# mini-v1_11-macrofab.net
KiCad netlist of a schematic drawn in EAGLE
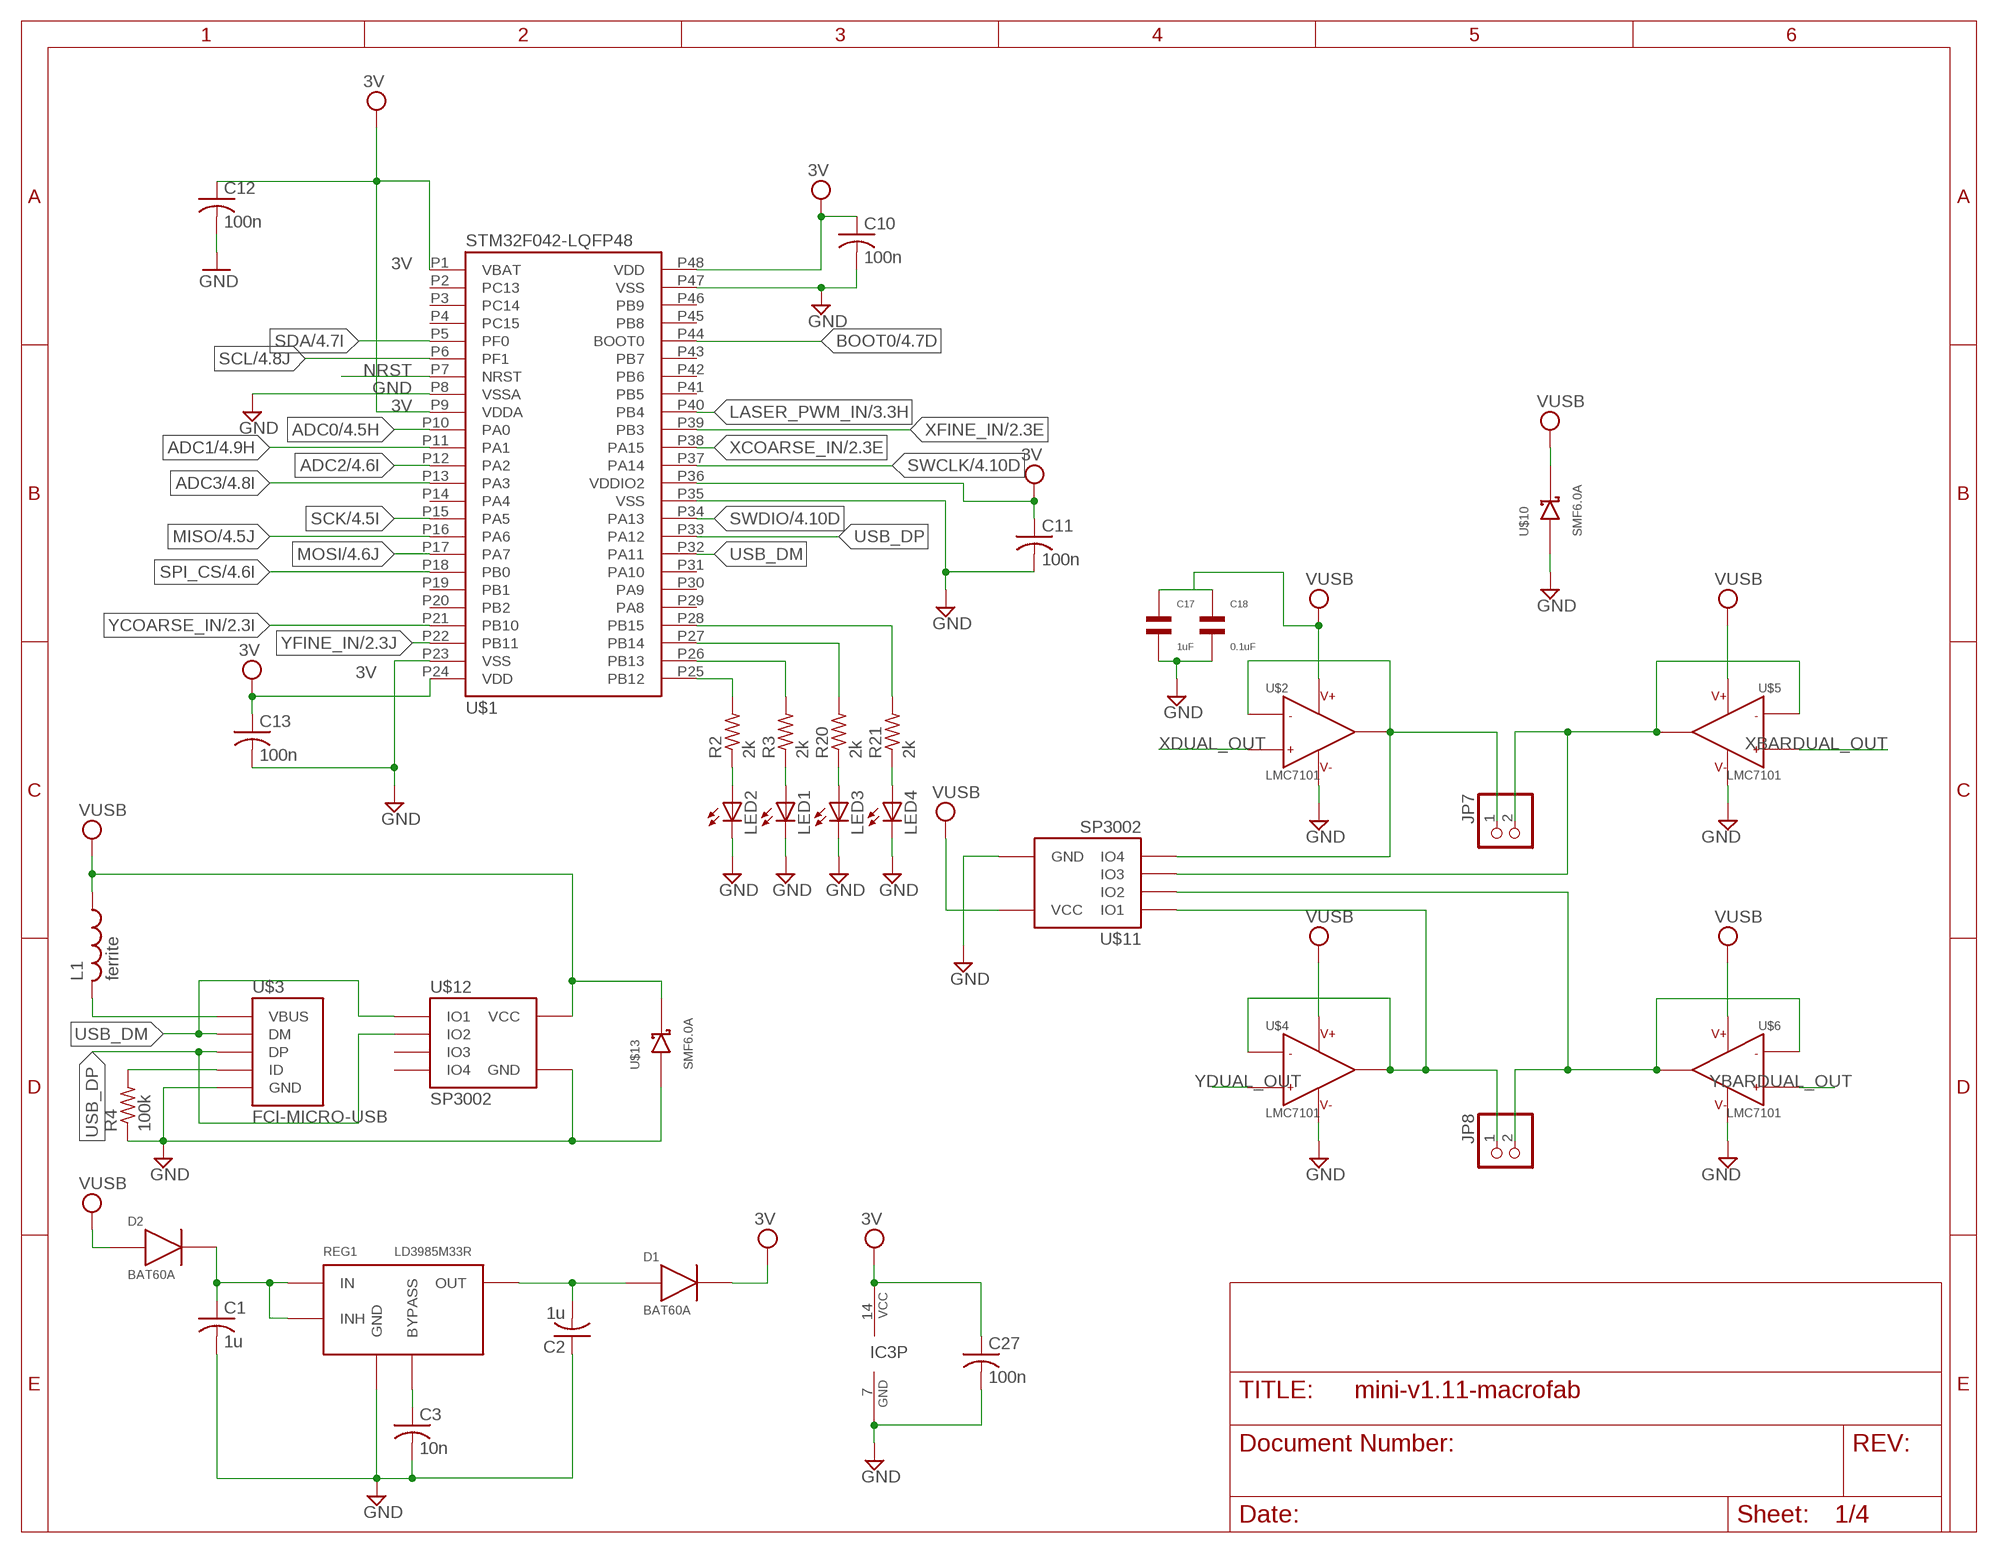
[diagram p0: schematic, sheet 1]
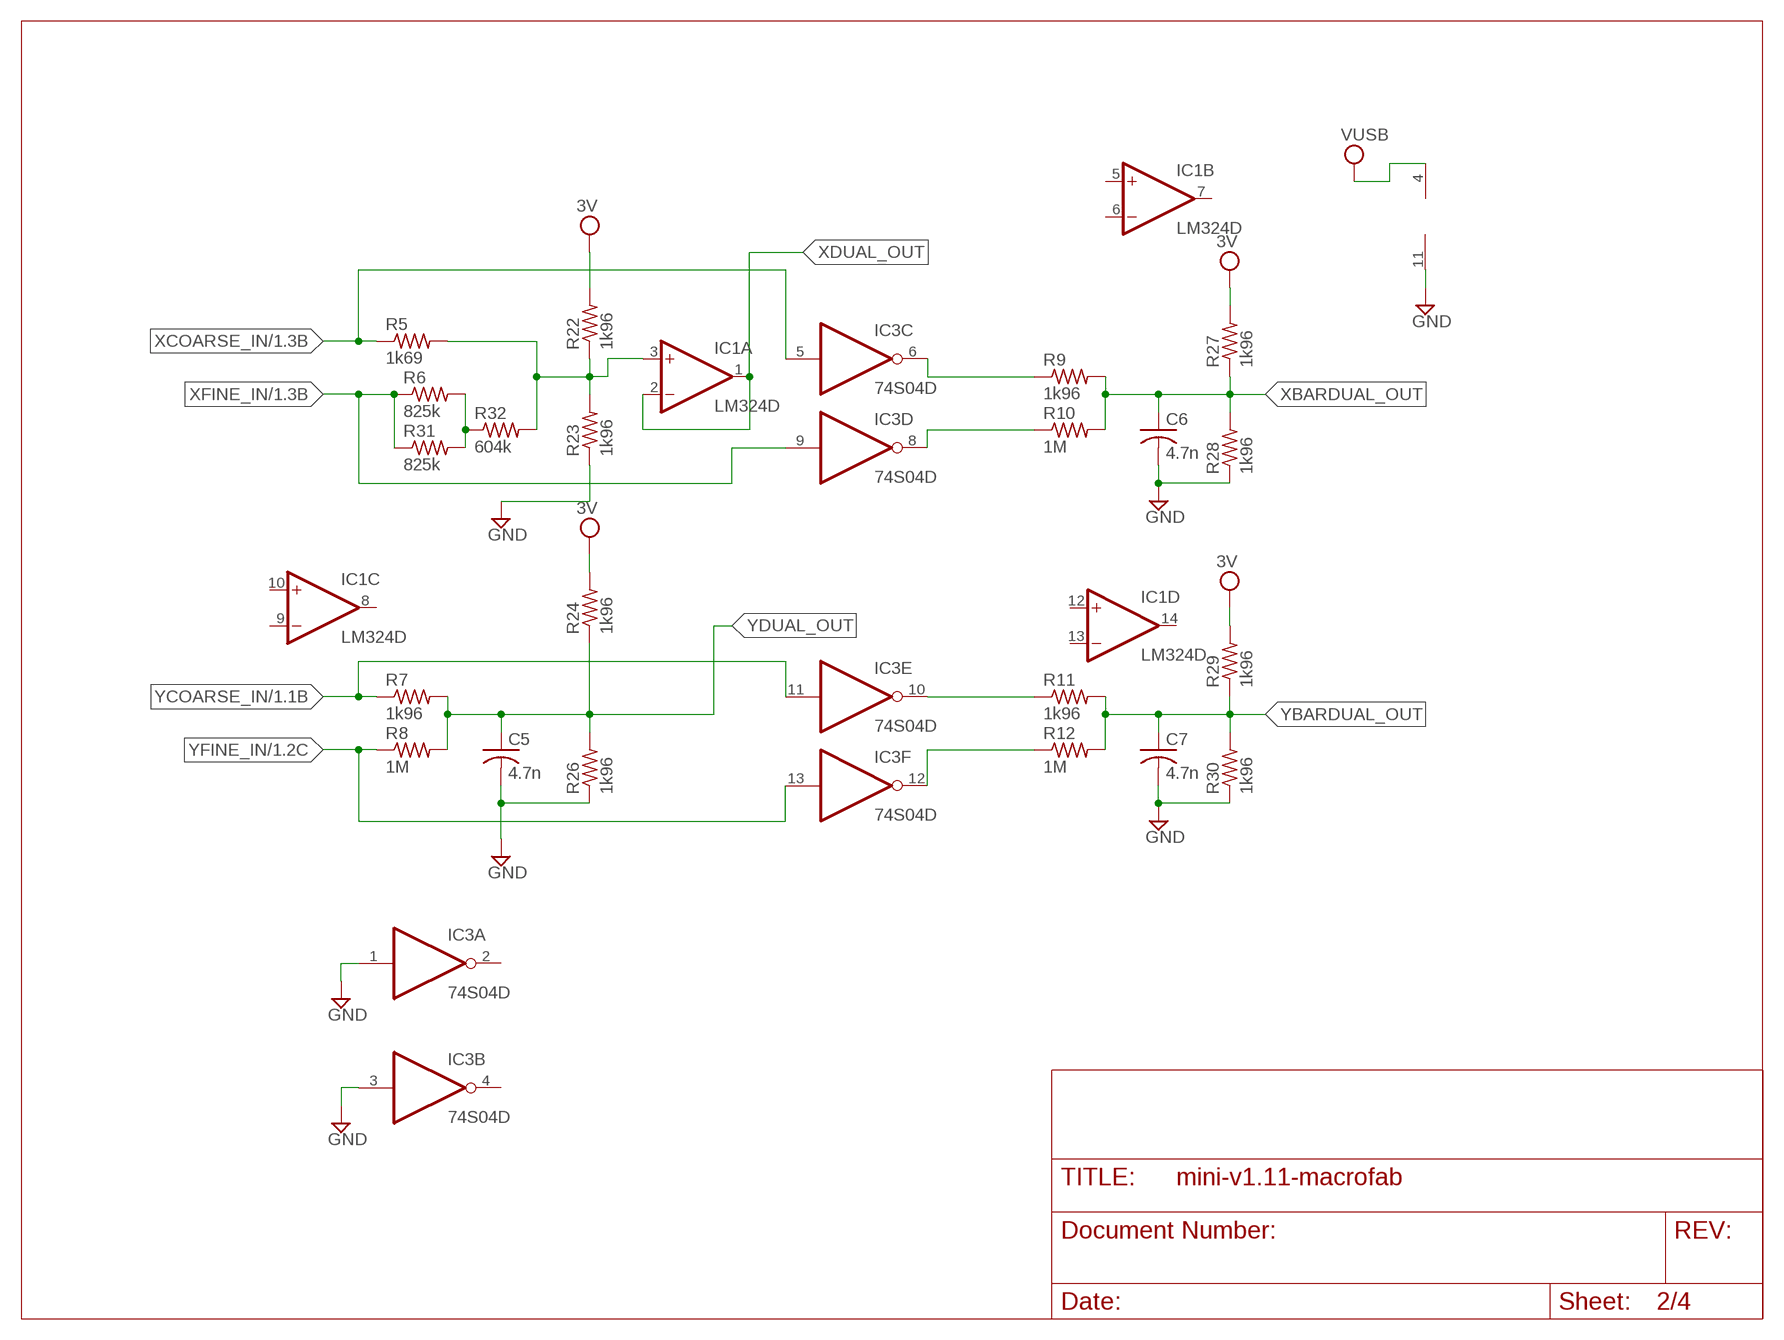
[diagram p1: schematic, sheet 2]
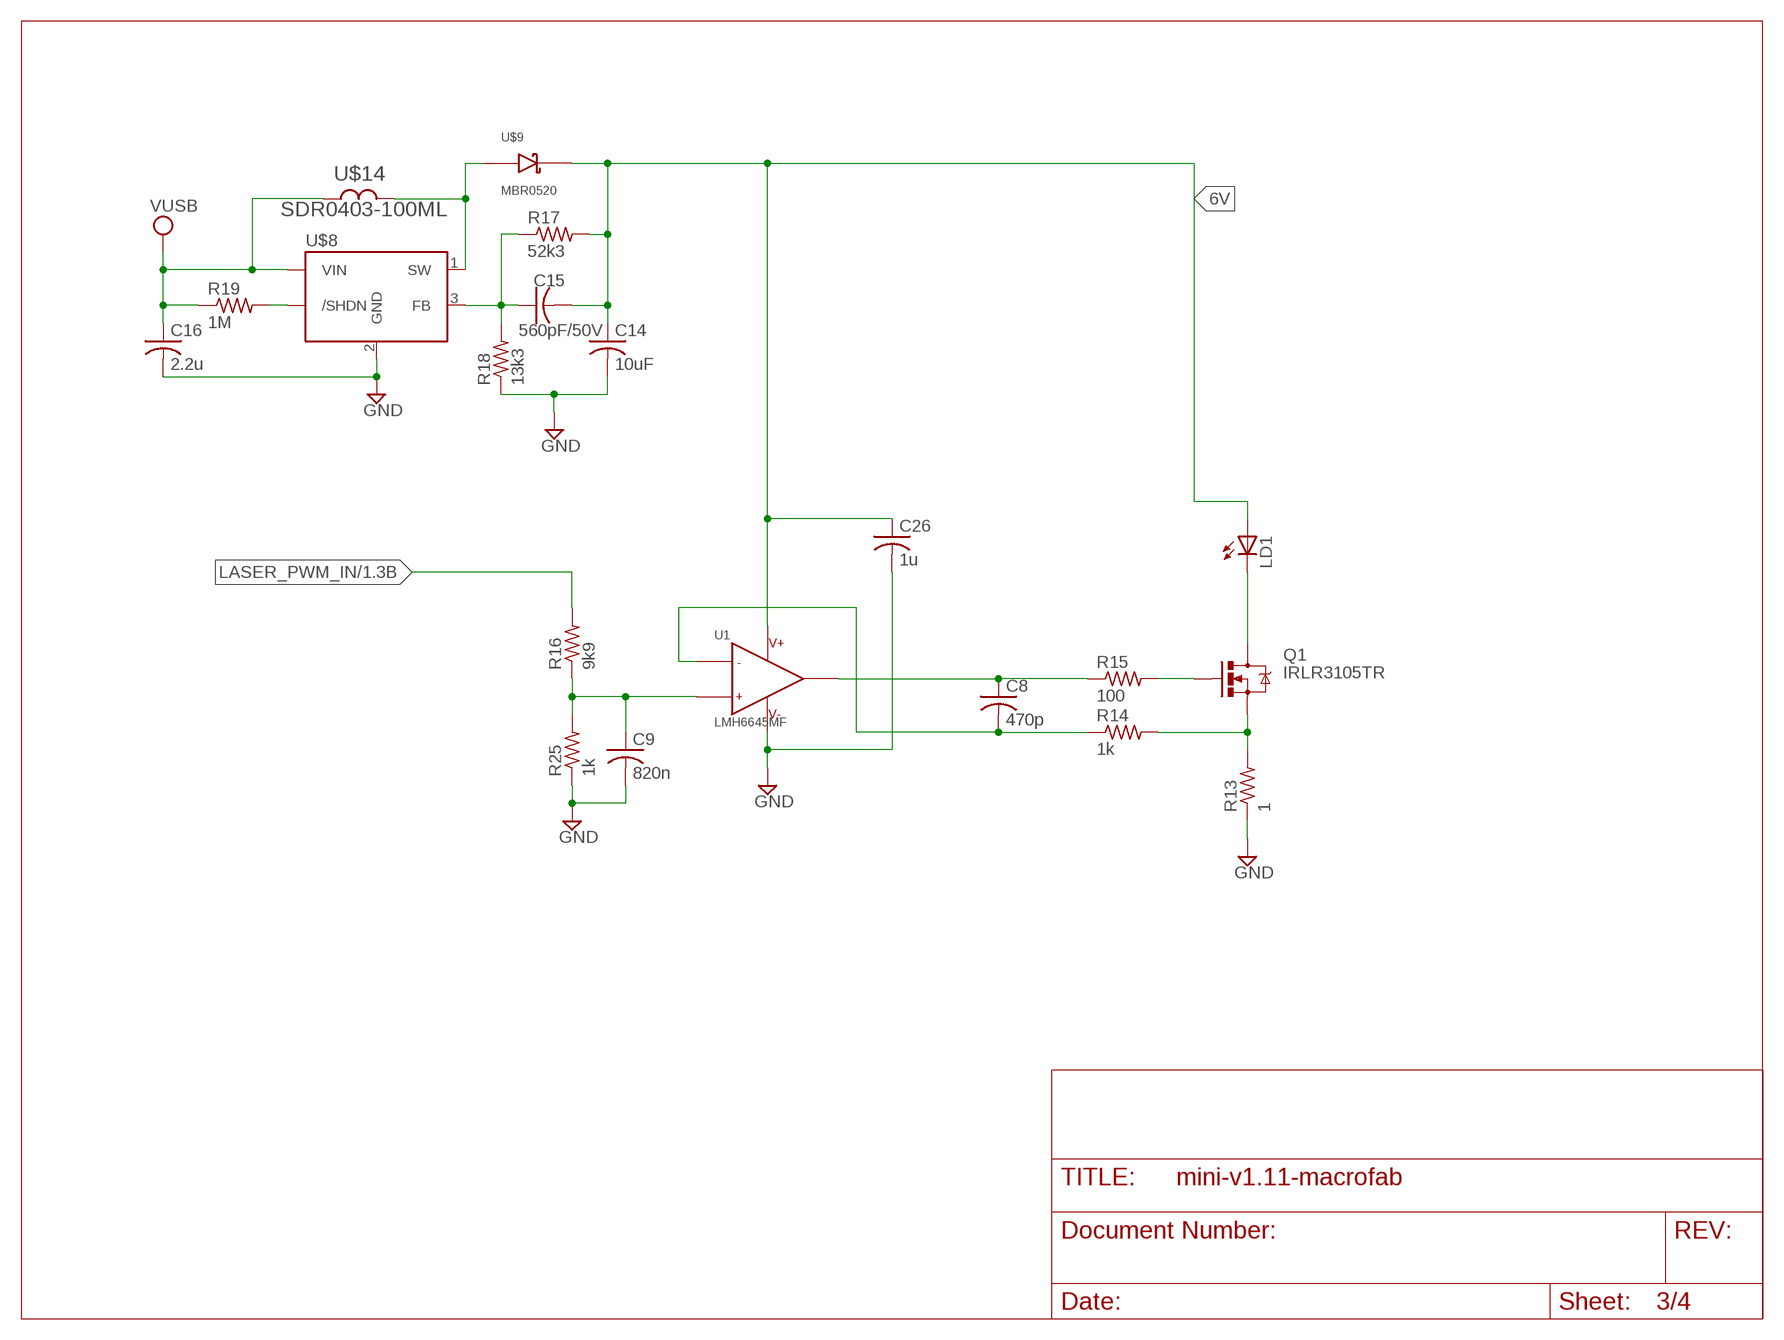
[diagram p2: schematic, sheet 3]
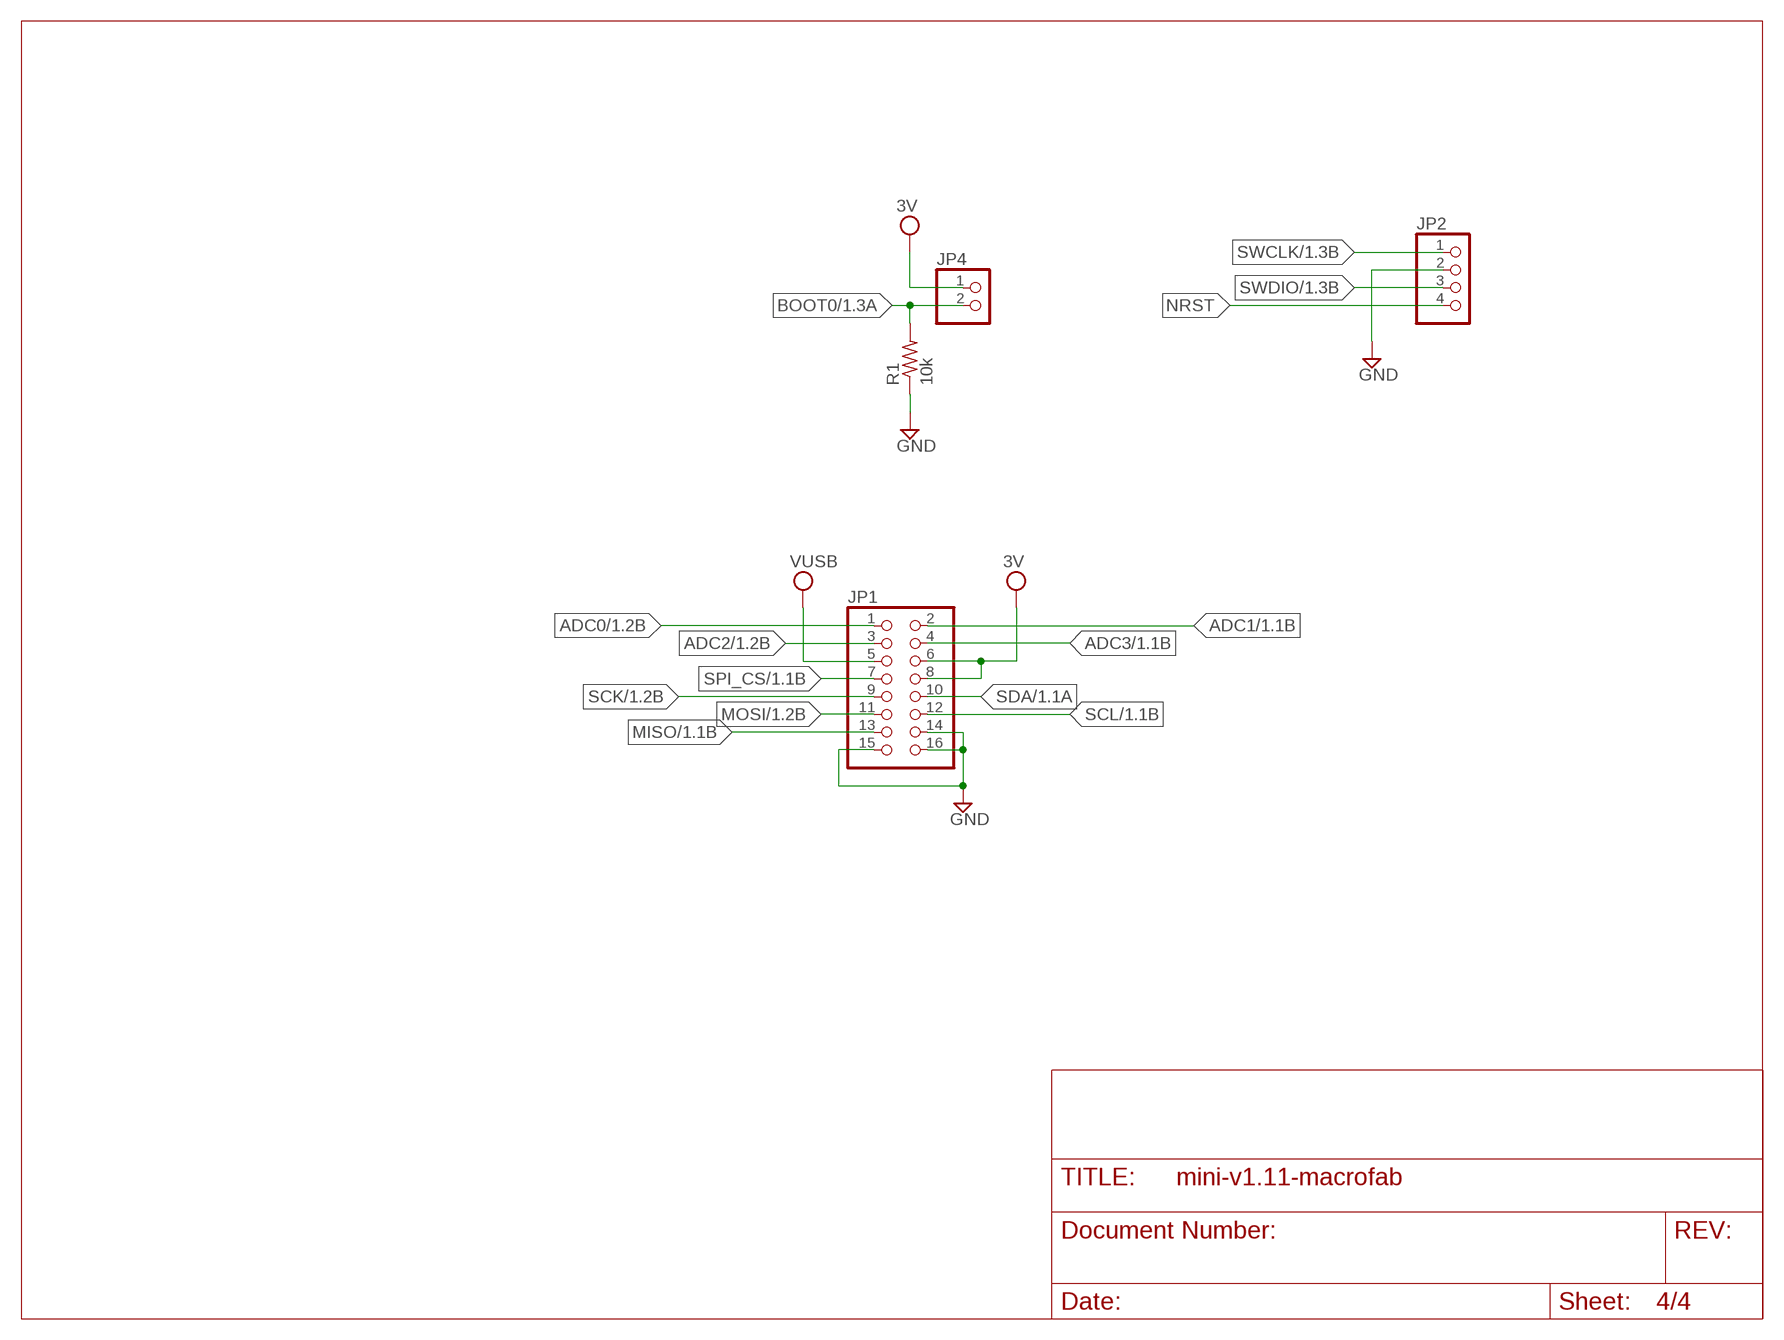
[diagram p3: schematic, sheet 4]

(export (version "E")
  (design (tool "Eeschema 10.0.6"))
  (components
    (comp (ref "C5")
      (value "4.7n")
      (footprint "eagle-import:C0603")
      (libsource (lib "eagle-import") (part "C-USC0603"))
    )
    (comp (ref "C6")
      (value "4.7n")
      (footprint "eagle-import:C0603")
      (libsource (lib "eagle-import") (part "C-USC0603"))
    )
    (comp (ref "C7")
      (value "4.7n")
      (footprint "eagle-import:C0603")
      (libsource (lib "eagle-import") (part "C-USC0603"))
    )
    (comp (ref "IC1")
      (value "LM324D")
      (footprint "eagle-import:SO14")
      (libsource (lib "eagle-import") (part "LM324D"))
    )
    (comp (ref "IC3")
      (value "74S04D")
      (footprint "eagle-import:SO14")
      (libsource (lib "eagle-import") (part "7404DS"))
    )
    (comp (ref "R5")
      (value "1k69")
      (footprint "eagle-import:R0603")
      (libsource (lib "eagle-import") (part "R-US_R0603"))
    )
    (comp (ref "R6")
      (value "825k")
      (footprint "eagle-import:R0603")
      (libsource (lib "eagle-import") (part "R-US_R0603"))
    )
    (comp (ref "R7")
      (value "1k96")
      (footprint "eagle-import:R0603")
      (libsource (lib "eagle-import") (part "R-US_R0603"))
    )
    (comp (ref "R8")
      (value "1M")
      (footprint "eagle-import:R0603")
      (libsource (lib "eagle-import") (part "R-US_R0603"))
    )
    (comp (ref "R9")
      (value "1k96")
      (footprint "eagle-import:R0603")
      (libsource (lib "eagle-import") (part "R-US_R0603"))
    )
    (comp (ref "R10")
      (value "1M")
      (footprint "eagle-import:R0603")
      (libsource (lib "eagle-import") (part "R-US_R0603"))
    )
    (comp (ref "R11")
      (value "1k96")
      (footprint "eagle-import:R0603")
      (libsource (lib "eagle-import") (part "R-US_R0603"))
    )
    (comp (ref "R12")
      (value "1M")
      (footprint "eagle-import:R0603")
      (libsource (lib "eagle-import") (part "R-US_R0603"))
    )
    (comp (ref "R22")
      (value "1k96")
      (footprint "eagle-import:R0603")
      (libsource (lib "eagle-import") (part "R-US_R0603"))
    )
    (comp (ref "R23")
      (value "1k96")
      (footprint "eagle-import:R0603")
      (libsource (lib "eagle-import") (part "R-US_R0603"))
    )
    (comp (ref "R24")
      (value "1k96")
      (footprint "eagle-import:R0603")
      (libsource (lib "eagle-import") (part "R-US_R0603"))
    )
    (comp (ref "R26")
      (value "1k96")
      (footprint "eagle-import:R0603")
      (libsource (lib "eagle-import") (part "R-US_R0603"))
    )
    (comp (ref "R27")
      (value "1k96")
      (footprint "eagle-import:R0603")
      (libsource (lib "eagle-import") (part "R-US_R0603"))
    )
    (comp (ref "R28")
      (value "1k96")
      (footprint "eagle-import:R0603")
      (libsource (lib "eagle-import") (part "R-US_R0603"))
    )
    (comp (ref "R29")
      (value "1k96")
      (footprint "eagle-import:R0603")
      (libsource (lib "eagle-import") (part "R-US_R0603"))
    )
    (comp (ref "R30")
      (value "1k96")
      (footprint "eagle-import:R0603")
      (libsource (lib "eagle-import") (part "R-US_R0603"))
    )
    (comp (ref "R31")
      (value "825k")
      (footprint "eagle-import:R0603")
      (libsource (lib "eagle-import") (part "R-US_R0603"))
    )
    (comp (ref "R32")
      (value "604k")
      (footprint "eagle-import:R0603")
      (libsource (lib "eagle-import") (part "R-US_R0603"))
    )
    (comp (ref "C8")
      (value "470p")
      (footprint "eagle-import:C0603")
      (libsource (lib "eagle-import") (part "C-USC0603"))
    )
    (comp (ref "C9")
      (value "820n")
      (footprint "eagle-import:C0603")
      (libsource (lib "eagle-import") (part "C-USC0603"))
    )
    (comp (ref "C14")
      (value "10uF")
      (footprint "eagle-import:C0603")
      (libsource (lib "eagle-import") (part "C-USC0603"))
    )
    (comp (ref "C15")
      (value "560pF/50V")
      (footprint "eagle-import:C0603")
      (libsource (lib "eagle-import") (part "C-USC0603"))
    )
    (comp (ref "C16")
      (value "2.2u")
      (footprint "eagle-import:C0603")
      (libsource (lib "eagle-import") (part "C-USC0603"))
    )
    (comp (ref "C26")
      (value "1u")
      (footprint "eagle-import:C0603")
      (libsource (lib "eagle-import") (part "C-USC0603"))
    )
    (comp (ref "LD1")
      (value "LASERDIODELD2")
      (footprint "eagle-import:LASERDIODE2")
      (fields (field (name "MPN") "3 x (0552-2-15-15-11-27-10-0)"))
      (libsource (lib "eagle-import") (part "LASERDIODELD2"))
    )
    (comp (ref "Q1")
      (value "IRLR3105TR")
      (footprint "eagle-import:DPAK")
      (libsource (lib "eagle-import") (part "FET-N-IRLR3105TRIRLR3105TR"))
    )
    (comp (ref "R13")
      (value "1")
      (footprint "eagle-import:R0603")
      (libsource (lib "eagle-import") (part "R-US_R0603"))
    )
    (comp (ref "R14")
      (value "1k")
      (footprint "eagle-import:R0603")
      (libsource (lib "eagle-import") (part "R-US_R0603"))
    )
    (comp (ref "R15")
      (value "100")
      (footprint "eagle-import:R0603")
      (libsource (lib "eagle-import") (part "R-US_R0603"))
    )
    (comp (ref "R16")
      (value "9k9")
      (footprint "eagle-import:R0603")
      (libsource (lib "eagle-import") (part "R-US_R0603"))
    )
    (comp (ref "R17")
      (value "52k3")
      (footprint "eagle-import:R0603")
      (libsource (lib "eagle-import") (part "R-US_R0603"))
    )
    (comp (ref "R18")
      (value "13k3")
      (footprint "eagle-import:R0603")
      (libsource (lib "eagle-import") (part "R-US_R0603"))
    )
    (comp (ref "R19")
      (value "1M")
      (footprint "eagle-import:R0603")
      (libsource (lib "eagle-import") (part "R-US_R0603"))
    )
    (comp (ref "R25")
      (value "1k")
      (footprint "eagle-import:R0603")
      (libsource (lib "eagle-import") (part "R-US_R0603"))
    )
    (comp (ref "U$8")
      (value "LMR62014")
      (footprint "eagle-import:SOT23-5")
      (libsource (lib "eagle-import") (part "LMR62014"))
    )
    (comp (ref "U$9")
      (value "MBR0520")
      (footprint "eagle-import:SOD123")
      (libsource (lib "eagle-import") (part "MBR0520"))
    )
    (comp (ref "U$14")
      (value "SDR0403-100ML")
      (footprint "eagle-import:SDR0403")
      (libsource (lib "eagle-import") (part "SDR0403"))
    )
    (comp (ref "U1")
      (value "LMH6645MF")
      (footprint "eagle-import:SOT23-5")
      (libsource (lib "eagle-import") (part "OPAMP-SINGLELMH6645MF"))
    )
    (comp (ref "JP1")
      (value "PINHD-2X8")
      (footprint "eagle-import:2X08")
      (libsource (lib "eagle-import") (part "PINHD-2X8"))
    )
    (comp (ref "JP2")
      (value "PINHD-1X4")
      (footprint "eagle-import:1X04")
      (libsource (lib "eagle-import") (part "PINHD-1X4"))
    )
    (comp (ref "JP4")
      (value "PINHD-1X2")
      (footprint "eagle-import:1X02")
      (libsource (lib "eagle-import") (part "PINHD-1X2"))
    )
    (comp (ref "R1")
      (value "10k")
      (footprint "eagle-import:R0603")
      (libsource (lib "eagle-import") (part "R-US_R0603"))
    )
    (comp (ref "C1")
      (value "1u")
      (footprint "eagle-import:C0603")
      (libsource (lib "eagle-import") (part "C-USC0603"))
    )
    (comp (ref "C2")
      (value "1u")
      (footprint "eagle-import:C0603")
      (libsource (lib "eagle-import") (part "C-USC0603"))
    )
    (comp (ref "C3")
      (value "10n")
      (footprint "eagle-import:C0603")
      (libsource (lib "eagle-import") (part "C-USC0603"))
    )
    (comp (ref "C10")
      (value "100n")
      (footprint "eagle-import:C0603")
      (libsource (lib "eagle-import") (part "C-USC0603"))
    )
    (comp (ref "C11")
      (value "100n")
      (footprint "eagle-import:C0603")
      (libsource (lib "eagle-import") (part "C-USC0603"))
    )
    (comp (ref "C12")
      (value "100n")
      (footprint "eagle-import:C0603")
      (libsource (lib "eagle-import") (part "C-USC0603"))
    )
    (comp (ref "C13")
      (value "100n")
      (footprint "eagle-import:C0603")
      (libsource (lib "eagle-import") (part "C-USC0603"))
    )
    (comp (ref "C17")
      (value "1uF")
      (footprint "eagle-import:C0603")
      (libsource (lib "eagle-import") (part "CAPACITOR_NP_0603"))
    )
    (comp (ref "C18")
      (value "0.1uF")
      (footprint "eagle-import:C0603")
      (libsource (lib "eagle-import") (part "CAPACITOR_NP_0603"))
    )
    (comp (ref "C27")
      (value "100n")
      (footprint "eagle-import:C0603")
      (libsource (lib "eagle-import") (part "C-USC0603"))
    )
    (comp (ref "D1")
      (value "BAT60A")
      (footprint "eagle-import:SOD323")
      (libsource (lib "eagle-import") (part "BAT60A"))
    )
    (comp (ref "D2")
      (value "BAT60A")
      (footprint "eagle-import:SOD323")
      (libsource (lib "eagle-import") (part "BAT60A"))
    )
    (comp (ref "JP7")
      (value "PINHD-1X2")
      (footprint "eagle-import:1X02")
      (libsource (lib "eagle-import") (part "PINHD-1X2"))
    )
    (comp (ref "JP8")
      (value "PINHD-1X2")
      (footprint "eagle-import:1X02")
      (libsource (lib "eagle-import") (part "PINHD-1X2"))
    )
    (comp (ref "L1")
      (value "ferrite")
      (footprint "eagle-import:C0603")
      (libsource (lib "eagle-import") (part "L-US"))
    )
    (comp (ref "LED1")
      (value "LEDCHIP-LED0603")
      (footprint "eagle-import:CHIP-LED0603")
      (libsource (lib "eagle-import") (part "LEDCHIP-LED0603"))
    )
    (comp (ref "LED2")
      (value "LEDCHIP-LED0603")
      (footprint "eagle-import:CHIP-LED0603")
      (libsource (lib "eagle-import") (part "LEDCHIP-LED0603"))
    )
    (comp (ref "LED3")
      (value "LEDCHIP-LED0603")
      (footprint "eagle-import:CHIP-LED0603")
      (libsource (lib "eagle-import") (part "LEDCHIP-LED0603"))
    )
    (comp (ref "LED4")
      (value "LEDCHIP-LED0603")
      (footprint "eagle-import:CHIP-LED0603")
      (libsource (lib "eagle-import") (part "LEDCHIP-LED0603"))
    )
    (comp (ref "R2")
      (value "2k")
      (footprint "eagle-import:R0603")
      (libsource (lib "eagle-import") (part "R-US_R0603"))
    )
    (comp (ref "R3")
      (value "2k")
      (footprint "eagle-import:R0603")
      (libsource (lib "eagle-import") (part "R-US_R0603"))
    )
    (comp (ref "R4")
      (value "100k")
      (footprint "eagle-import:R0603")
      (libsource (lib "eagle-import") (part "R-US_R0603"))
    )
    (comp (ref "R20")
      (value "2k")
      (footprint "eagle-import:R0603")
      (libsource (lib "eagle-import") (part "R-US_R0603"))
    )
    (comp (ref "R21")
      (value "2k")
      (footprint "eagle-import:R0603")
      (libsource (lib "eagle-import") (part "R-US_R0603"))
    )
    (comp (ref "REG1")
      (value "LD3985M33R")
      (footprint "eagle-import:SOT23-5L")
      (libsource (lib "eagle-import") (part "LD3985MXXR"))
    )
    (comp (ref "U$1")
      (value "STM32F042-LQFP48")
      (footprint "eagle-import:LQFP48")
      (libsource (lib "eagle-import") (part "STM32F042-LQFP48"))
    )
    (comp (ref "U$2")
      (value "LMC7101")
      (footprint "eagle-import:SOT23-5")
      (libsource (lib "eagle-import") (part "LMC7101"))
    )
    (comp (ref "U$3")
      (value "FCI-MICRO-USB")
      (footprint "eagle-import:FCI-MICROUSB")
      (libsource (lib "eagle-import") (part "FCI-MICRO-USB"))
    )
    (comp (ref "U$4")
      (value "LMC7101")
      (footprint "eagle-import:SOT23-5")
      (libsource (lib "eagle-import") (part "LMC7101"))
    )
    (comp (ref "U$5")
      (value "LMC7101")
      (footprint "eagle-import:SOT23-5")
      (libsource (lib "eagle-import") (part "LMC7101"))
    )
    (comp (ref "U$6")
      (value "LMC7101")
      (footprint "eagle-import:SOT23-5")
      (libsource (lib "eagle-import") (part "LMC7101"))
    )
    (comp (ref "U$10")
      (value "SMF6.0A")
      (footprint "eagle-import:SOD123")
      (libsource (lib "eagle-import") (part "MBR0520"))
    )
    (comp (ref "U$11")
      (value "SP3002")
      (footprint "eagle-import:SC70-6")
      (libsource (lib "eagle-import") (part "SP3002"))
    )
    (comp (ref "U$12")
      (value "SP3002")
      (footprint "eagle-import:SC70-6")
      (libsource (lib "eagle-import") (part "SP3002"))
    )
    (comp (ref "U$13")
      (value "SMF6.0A")
      (footprint "eagle-import:SOD123")
      (libsource (lib "eagle-import") (part "MBR0520"))
    )
  )
  (nets
    (net (code "1") (name "3V") (class "Default")
      (node (ref "C10") (pin "1") (pinfunction "1_1") (pintype "passive"))
      (node (ref "C11") (pin "1") (pinfunction "1_1") (pintype "passive"))
      (node (ref "C12") (pin "1") (pinfunction "1_1") (pintype "passive"))
      (node (ref "C13") (pin "1") (pinfunction "1_1") (pintype "passive"))
      (node (ref "C27") (pin "1") (pinfunction "1_1") (pintype "passive"))
      (node (ref "D1") (pin "1") (pinfunction "1_1") (pintype "bidirectional"))
      (node (ref "IC3") (pin "14") (pinfunction "VCC_14") (pintype "power_in"))
      (node (ref "JP1") (pin "6") (pinfunction "6_6") (pintype "passive"))
      (node (ref "JP1") (pin "8") (pinfunction "8_8") (pintype "passive"))
      (node (ref "JP4") (pin "1") (pinfunction "1_1") (pintype "passive"))
      (node (ref "R22") (pin "2") (pinfunction "2_2") (pintype "passive"))
      (node (ref "R24") (pin "2") (pinfunction "2_2") (pintype "passive"))
      (node (ref "R27") (pin "2") (pinfunction "2_2") (pintype "passive"))
      (node (ref "R29") (pin "2") (pinfunction "2_2") (pintype "passive"))
      (node (ref "U$1") (pin "P1") (pinfunction "VBAT_P1") (pintype "bidirectional"))
      (node (ref "U$1") (pin "P24") (pinfunction "VDD_P24") (pintype "bidirectional"))
      (node (ref "U$1") (pin "P36") (pinfunction "VDDIO2_P36") (pintype "bidirectional"))
      (node (ref "U$1") (pin "P48") (pinfunction "VDD_P48") (pintype "bidirectional"))
      (node (ref "U$1") (pin "P9") (pinfunction "VDDA_P9") (pintype "bidirectional"))
    )
    (net (code "2") (name "6V") (class "Default")
      (node (ref "C14") (pin "1") (pinfunction "1_1") (pintype "passive"))
      (node (ref "C15") (pin "2") (pinfunction "2_2") (pintype "passive"))
      (node (ref "C26") (pin "1") (pinfunction "1_1") (pintype "passive"))
      (node (ref "LD1") (pin "P$1") (pinfunction "A_P$1") (pintype "passive"))
      (node (ref "R17") (pin "2") (pinfunction "2_2") (pintype "passive"))
      (node (ref "U$9") (pin "CATHODE") (pinfunction "CATHODE_CATHODE") (pintype "bidirectional"))
      (node (ref "U1") (pin "5") (pinfunction "V+_5") (pintype "power_in"))
    )
    (net (code "3") (name "ADC0") (class "Default")
      (node (ref "JP1") (pin "1") (pinfunction "1_1") (pintype "passive"))
      (node (ref "U$1") (pin "P10") (pinfunction "PA0_P10") (pintype "bidirectional"))
    )
    (net (code "4") (name "ADC1") (class "Default")
      (node (ref "JP1") (pin "2") (pinfunction "2_2") (pintype "passive"))
      (node (ref "U$1") (pin "P11") (pinfunction "PA1_P11") (pintype "bidirectional"))
    )
    (net (code "5") (name "ADC2") (class "Default")
      (node (ref "JP1") (pin "3") (pinfunction "3_3") (pintype "passive"))
      (node (ref "U$1") (pin "P12") (pinfunction "PA2_P12") (pintype "bidirectional"))
    )
    (net (code "6") (name "ADC3") (class "Default")
      (node (ref "JP1") (pin "4") (pinfunction "4_4") (pintype "passive"))
      (node (ref "U$1") (pin "P13") (pinfunction "PA3_P13") (pintype "bidirectional"))
    )
    (net (code "7") (name "BOOT0") (class "Default")
      (node (ref "JP4") (pin "2") (pinfunction "2_2") (pintype "passive"))
      (node (ref "R1") (pin "2") (pinfunction "2_2") (pintype "passive"))
      (node (ref "U$1") (pin "P44") (pinfunction "BOOT0_P44") (pintype "bidirectional"))
    )
    (net (code "8") (name "GND") (class "Default")
      (node (ref "C1") (pin "2") (pinfunction "2_2") (pintype "passive"))
      (node (ref "C10") (pin "2") (pinfunction "2_2") (pintype "passive"))
      (node (ref "C11") (pin "2") (pinfunction "2_2") (pintype "passive"))
      (node (ref "C12") (pin "2") (pinfunction "2_2") (pintype "passive"))
      (node (ref "C13") (pin "2") (pinfunction "2_2") (pintype "passive"))
      (node (ref "C14") (pin "2") (pinfunction "2_2") (pintype "passive"))
      (node (ref "C16") (pin "2") (pinfunction "2_2") (pintype "passive"))
      (node (ref "C17") (pin "P$2") (pinfunction "P$2_P$2") (pintype "passive"))
      (node (ref "C18") (pin "P$2") (pinfunction "P$2_P$2") (pintype "passive"))
      (node (ref "C2") (pin "1") (pinfunction "1_1") (pintype "passive"))
      (node (ref "C26") (pin "2") (pinfunction "2_2") (pintype "passive"))
      (node (ref "C27") (pin "2") (pinfunction "2_2") (pintype "passive"))
      (node (ref "C3") (pin "2") (pinfunction "2_2") (pintype "passive"))
      (node (ref "C5") (pin "2") (pinfunction "2_2") (pintype "passive"))
      (node (ref "C6") (pin "2") (pinfunction "2_2") (pintype "passive"))
      (node (ref "C7") (pin "2") (pinfunction "2_2") (pintype "passive"))
      (node (ref "C9") (pin "2") (pinfunction "2_2") (pintype "passive"))
      (node (ref "IC1") (pin "11") (pinfunction "V-_11") (pintype "power_in"))
      (node (ref "IC3") (pin "1") (pinfunction "I_1") (pintype "input"))
      (node (ref "IC3") (pin "3") (pinfunction "I_3") (pintype "input"))
      (node (ref "IC3") (pin "7") (pinfunction "GND_7") (pintype "power_in"))
      (node (ref "JP1") (pin "14") (pinfunction "14_14") (pintype "passive"))
      (node (ref "JP1") (pin "15") (pinfunction "15_15") (pintype "passive"))
      (node (ref "JP1") (pin "16") (pinfunction "16_16") (pintype "passive"))
      (node (ref "JP2") (pin "2") (pinfunction "2_2") (pintype "passive"))
      (node (ref "LED1") (pin "C") (pinfunction "C_C") (pintype "passive"))
      (node (ref "LED2") (pin "C") (pinfunction "C_C") (pintype "passive"))
      (node (ref "LED3") (pin "C") (pinfunction "C_C") (pintype "passive"))
      (node (ref "LED4") (pin "C") (pinfunction "C_C") (pintype "passive"))
      (node (ref "R1") (pin "1") (pinfunction "1_1") (pintype "passive"))
      (node (ref "R13") (pin "1") (pinfunction "1_1") (pintype "passive"))
      (node (ref "R18") (pin "1") (pinfunction "1_1") (pintype "passive"))
      (node (ref "R23") (pin "1") (pinfunction "1_1") (pintype "passive"))
      (node (ref "R25") (pin "1") (pinfunction "1_1") (pintype "passive"))
      (node (ref "R26") (pin "1") (pinfunction "1_1") (pintype "passive"))
      (node (ref "R28") (pin "1") (pinfunction "1_1") (pintype "passive"))
      (node (ref "R30") (pin "1") (pinfunction "1_1") (pintype "passive"))
      (node (ref "R4") (pin "1") (pinfunction "1_1") (pintype "passive"))
      (node (ref "REG1") (pin "GND") (pinfunction "GND_GND") (pintype "bidirectional"))
      (node (ref "U$1") (pin "P23") (pinfunction "VSS_P23") (pintype "bidirectional"))
      (node (ref "U$1") (pin "P35") (pinfunction "VSS_P35") (pintype "bidirectional"))
      (node (ref "U$1") (pin "P47") (pinfunction "VSS_P47") (pintype "bidirectional"))
      (node (ref "U$1") (pin "P8") (pinfunction "VSSA_P8") (pintype "bidirectional"))
      (node (ref "U$10") (pin "ANODE") (pinfunction "ANODE_ANODE") (pintype "bidirectional"))
      (node (ref "U$11") (pin "P2") (pinfunction "GND_P2") (pintype "power_in"))
      (node (ref "U$12") (pin "P2") (pinfunction "GND_P2") (pintype "power_in"))
      (node (ref "U$13") (pin "ANODE") (pinfunction "ANODE_ANODE") (pintype "bidirectional"))
      (node (ref "U$2") (pin "5") (pinfunction "P5_5") (pintype "power_in"))
      (node (ref "U$3") (pin "P5") (pinfunction "GND_P5") (pintype "bidirectional"))
      (node (ref "U$4") (pin "5") (pinfunction "P5_5") (pintype "power_in"))
      (node (ref "U$5") (pin "5") (pinfunction "P5_5") (pintype "power_in"))
      (node (ref "U$6") (pin "5") (pinfunction "P5_5") (pintype "power_in"))
      (node (ref "U$8") (pin "2") (pinfunction "GND_2") (pintype "bidirectional"))
      (node (ref "U1") (pin "2") (pinfunction "V-_2") (pintype "power_in"))
    )
    (net (code "9") (name "LASER_PWM_IN") (class "Default")
      (node (ref "R16") (pin "2") (pinfunction "2_2") (pintype "passive"))
      (node (ref "U$1") (pin "P40") (pinfunction "PB4_P40") (pintype "bidirectional"))
    )
    (net (code "10") (name "MISO") (class "Default")
      (node (ref "JP1") (pin "13") (pinfunction "13_13") (pintype "passive"))
      (node (ref "U$1") (pin "P16") (pinfunction "PA6_P16") (pintype "bidirectional"))
    )
    (net (code "11") (name "MOSI") (class "Default")
      (node (ref "JP1") (pin "11") (pinfunction "11_11") (pintype "passive"))
      (node (ref "U$1") (pin "P17") (pinfunction "PA7_P17") (pintype "bidirectional"))
    )
    (net (code "12") (name "NRST") (class "Default")
      (node (ref "JP2") (pin "4") (pinfunction "4_4") (pintype "passive"))
      (node (ref "U$1") (pin "P7") (pinfunction "NRST_P7") (pintype "bidirectional"))
    )
    (net (code "13") (name "Net-(C2-Pad2)") (class "Default")
      (node (ref "C2") (pin "2") (pinfunction "2_2") (pintype "passive"))
      (node (ref "D1") (pin "2") (pinfunction "2_2") (pintype "bidirectional"))
      (node (ref "REG1") (pin "OUT") (pinfunction "OUT_OUT") (pintype "bidirectional"))
    )
    (net (code "14") (name "Net-(C3-Pad1)") (class "Default")
      (node (ref "C3") (pin "1") (pinfunction "1_1") (pintype "passive"))
      (node (ref "REG1") (pin "BYPASS") (pinfunction "BYPASS_BYPASS") (pintype "bidirectional"))
    )
    (net (code "15") (name "Net-(IC1A-+IN)") (class "Default")
      (node (ref "IC1") (pin "3") (pinfunction "+IN_3") (pintype "input"))
      (node (ref "R22") (pin "1") (pinfunction "1_1") (pintype "passive"))
      (node (ref "R23") (pin "2") (pinfunction "2_2") (pintype "passive"))
      (node (ref "R32") (pin "2") (pinfunction "2_2") (pintype "passive"))
      (node (ref "R5") (pin "2") (pinfunction "2_2") (pintype "passive"))
    )
    (net (code "16") (name "Net-(IC3C-O)") (class "Default")
      (node (ref "IC3") (pin "6") (pinfunction "O_6") (pintype "output"))
      (node (ref "R9") (pin "1") (pinfunction "1_1") (pintype "passive"))
    )
    (net (code "17") (name "Net-(IC3D-O)") (class "Default")
      (node (ref "IC3") (pin "8") (pinfunction "O_8") (pintype "output"))
      (node (ref "R10") (pin "1") (pinfunction "1_1") (pintype "passive"))
    )
    (net (code "18") (name "Net-(IC3E-O)") (class "Default")
      (node (ref "IC3") (pin "10") (pinfunction "O_10") (pintype "output"))
      (node (ref "R11") (pin "1") (pinfunction "1_1") (pintype "passive"))
    )
    (net (code "19") (name "Net-(IC3F-O)") (class "Default")
      (node (ref "IC3") (pin "12") (pinfunction "O_12") (pintype "output"))
      (node (ref "R12") (pin "1") (pinfunction "1_1") (pintype "passive"))
    )
    (net (code "20") (name "Net-(LD1-C)") (class "Default")
      (node (ref "LD1") (pin "P$3") (pinfunction "C_P$3") (pintype "passive"))
      (node (ref "Q1") (pin "4") (pinfunction "D_4") (pintype "passive"))
    )
    (net (code "21") (name "Net-(LED1-PadA)") (class "Default")
      (node (ref "LED1") (pin "A") (pinfunction "A_A") (pintype "passive"))
      (node (ref "R3") (pin "1") (pinfunction "1_1") (pintype "passive"))
    )
    (net (code "22") (name "Net-(LED2-PadA)") (class "Default")
      (node (ref "LED2") (pin "A") (pinfunction "A_A") (pintype "passive"))
      (node (ref "R2") (pin "1") (pinfunction "1_1") (pintype "passive"))
    )
    (net (code "23") (name "Net-(LED3-PadA)") (class "Default")
      (node (ref "LED3") (pin "A") (pinfunction "A_A") (pintype "passive"))
      (node (ref "R20") (pin "1") (pinfunction "1_1") (pintype "passive"))
    )
    (net (code "24") (name "Net-(LED4-PadA)") (class "Default")
      (node (ref "LED4") (pin "A") (pinfunction "A_A") (pintype "passive"))
      (node (ref "R21") (pin "1") (pinfunction "1_1") (pintype "passive"))
    )
    (net (code "25") (name "Net-(Q1-G)") (class "Default")
      (node (ref "Q1") (pin "1") (pinfunction "G_1") (pintype "passive"))
      (node (ref "R15") (pin "2") (pinfunction "2_2") (pintype "passive"))
    )
    (net (code "26") (name "Net-(Q1-S)") (class "Default")
      (node (ref "Q1") (pin "3") (pinfunction "S_3") (pintype "passive"))
      (node (ref "R13") (pin "2") (pinfunction "2_2") (pintype "passive"))
      (node (ref "R14") (pin "2") (pinfunction "2_2") (pintype "passive"))
    )
    (net (code "27") (name "Net-(R31-Pad2)") (class "Default")
      (node (ref "R31") (pin "2") (pinfunction "2_2") (pintype "passive"))
      (node (ref "R32") (pin "1") (pinfunction "1_1") (pintype "passive"))
      (node (ref "R6") (pin "2") (pinfunction "2_2") (pintype "passive"))
    )
    (net (code "28") (name "Net-(REG1-INH)") (class "Default")
      (node (ref "C1") (pin "1") (pinfunction "1_1") (pintype "passive"))
      (node (ref "D2") (pin "1") (pinfunction "1_1") (pintype "bidirectional"))
      (node (ref "REG1") (pin "IN") (pinfunction "IN_IN") (pintype "bidirectional"))
      (node (ref "REG1") (pin "INHIBIT") (pinfunction "INH_INHIBIT") (pintype "bidirectional"))
    )
    (net (code "29") (name "Net-(U$1-PB12)") (class "Default")
      (node (ref "R2") (pin "2") (pinfunction "2_2") (pintype "passive"))
      (node (ref "U$1") (pin "P25") (pinfunction "PB12_P25") (pintype "bidirectional"))
    )
    (net (code "30") (name "Net-(U$1-PB13)") (class "Default")
      (node (ref "R3") (pin "2") (pinfunction "2_2") (pintype "passive"))
      (node (ref "U$1") (pin "P26") (pinfunction "PB13_P26") (pintype "bidirectional"))
    )
    (net (code "31") (name "Net-(U$1-PB14)") (class "Default")
      (node (ref "R20") (pin "2") (pinfunction "2_2") (pintype "passive"))
      (node (ref "U$1") (pin "P27") (pinfunction "PB14_P27") (pintype "bidirectional"))
    )
    (net (code "32") (name "Net-(U$1-PB15)") (class "Default")
      (node (ref "R21") (pin "2") (pinfunction "2_2") (pintype "passive"))
      (node (ref "U$1") (pin "P28") (pinfunction "PB15_P28") (pintype "bidirectional"))
    )
    (net (code "33") (name "Net-(U$3-ID)") (class "Default")
      (node (ref "R4") (pin "2") (pinfunction "2_2") (pintype "passive"))
      (node (ref "U$3") (pin "P4") (pinfunction "ID_P4") (pintype "bidirectional"))
    )
    (net (code "34") (name "Net-(U$3-VBUS)") (class "Default")
      (node (ref "L1") (pin "2") (pinfunction "2_2") (pintype "passive"))
      (node (ref "U$3") (pin "P1") (pinfunction "VBUS_P1") (pintype "bidirectional"))
    )
    (net (code "35") (name "Net-(U$8-FB)") (class "Default")
      (node (ref "C15") (pin "1") (pinfunction "1_1") (pintype "passive"))
      (node (ref "R17") (pin "1") (pinfunction "1_1") (pintype "passive"))
      (node (ref "R18") (pin "2") (pinfunction "2_2") (pintype "passive"))
      (node (ref "U$8") (pin "3") (pinfunction "FB_3") (pintype "bidirectional"))
    )
    (net (code "36") (name "Net-(U$8-SW)") (class "Default")
      (node (ref "U$14") (pin "P$2") (pinfunction "P$2_P$2") (pintype "bidirectional"))
      (node (ref "U$8") (pin "1") (pinfunction "SW_1") (pintype "bidirectional"))
      (node (ref "U$9") (pin "ANODE") (pinfunction "ANODE_ANODE") (pintype "bidirectional"))
    )
    (net (code "37") (name "Net-(U$8-{slash}SHDN)") (class "Default")
      (node (ref "R19") (pin "2") (pinfunction "2_2") (pintype "passive"))
      (node (ref "U$8") (pin "4") (pinfunction "/SHDN_4") (pintype "bidirectional"))
    )
    (net (code "38") (name "Net-(U$11-IO1)") (class "Default")
      (node (ref "JP8") (pin "1") (pinfunction "1_1") (pintype "passive"))
      (node (ref "U$11") (pin "P1") (pinfunction "IO1_P1") (pintype "bidirectional"))
      (node (ref "U$4") (pin "1") (pinfunction "P1_1") (pintype "bidirectional"))
      (node (ref "U$4") (pin "4") (pinfunction "P4_4") (pintype "bidirectional"))
    )
    (net (code "39") (name "Net-(U$11-IO2)") (class "Default")
      (node (ref "JP8") (pin "2") (pinfunction "2_2") (pintype "passive"))
      (node (ref "U$11") (pin "P3") (pinfunction "IO2_P3") (pintype "bidirectional"))
      (node (ref "U$6") (pin "1") (pinfunction "P1_1") (pintype "bidirectional"))
      (node (ref "U$6") (pin "4") (pinfunction "P4_4") (pintype "bidirectional"))
    )
    (net (code "40") (name "Net-(U$11-IO3)") (class "Default")
      (node (ref "JP7") (pin "2") (pinfunction "2_2") (pintype "passive"))
      (node (ref "U$11") (pin "P4") (pinfunction "IO3_P4") (pintype "bidirectional"))
      (node (ref "U$5") (pin "1") (pinfunction "P1_1") (pintype "bidirectional"))
      (node (ref "U$5") (pin "4") (pinfunction "P4_4") (pintype "bidirectional"))
    )
    (net (code "41") (name "Net-(U$11-IO4)") (class "Default")
      (node (ref "JP7") (pin "1") (pinfunction "1_1") (pintype "passive"))
      (node (ref "U$11") (pin "P6") (pinfunction "IO4_P6") (pintype "bidirectional"))
      (node (ref "U$2") (pin "1") (pinfunction "P1_1") (pintype "bidirectional"))
      (node (ref "U$2") (pin "4") (pinfunction "P4_4") (pintype "bidirectional"))
    )
    (net (code "42") (name "Net-(U1-IN+)") (class "Default")
      (node (ref "C9") (pin "1") (pinfunction "1_1") (pintype "passive"))
      (node (ref "R16") (pin "1") (pinfunction "1_1") (pintype "passive"))
      (node (ref "R25") (pin "2") (pinfunction "2_2") (pintype "passive"))
      (node (ref "U1") (pin "3") (pinfunction "IN+_3") (pintype "bidirectional"))
    )
    (net (code "43") (name "Net-(U1-IN-)") (class "Default")
      (node (ref "C8") (pin "2") (pinfunction "2_2") (pintype "passive"))
      (node (ref "R14") (pin "1") (pinfunction "1_1") (pintype "passive"))
      (node (ref "U1") (pin "4") (pinfunction "IN-_4") (pintype "bidirectional"))
    )
    (net (code "44") (name "Net-(U1-OUT)") (class "Default")
      (node (ref "C8") (pin "1") (pinfunction "1_1") (pintype "passive"))
      (node (ref "R15") (pin "1") (pinfunction "1_1") (pintype "passive"))
      (node (ref "U1") (pin "1") (pinfunction "OUT_1") (pintype "bidirectional"))
    )
    (net (code "45") (name "SCK") (class "Default")
      (node (ref "JP1") (pin "9") (pinfunction "9_9") (pintype "passive"))
      (node (ref "U$1") (pin "P15") (pinfunction "PA5_P15") (pintype "bidirectional"))
    )
    (net (code "46") (name "SCL") (class "Default")
      (node (ref "JP1") (pin "12") (pinfunction "12_12") (pintype "passive"))
      (node (ref "U$1") (pin "P6") (pinfunction "PF1_P6") (pintype "bidirectional"))
    )
    (net (code "47") (name "SDA") (class "Default")
      (node (ref "JP1") (pin "10") (pinfunction "10_10") (pintype "passive"))
      (node (ref "U$1") (pin "P5") (pinfunction "PF0_P5") (pintype "bidirectional"))
    )
    (net (code "48") (name "SPI_CS") (class "Default")
      (node (ref "JP1") (pin "7") (pinfunction "7_7") (pintype "passive"))
      (node (ref "U$1") (pin "P18") (pinfunction "PB0_P18") (pintype "bidirectional"))
    )
    (net (code "49") (name "SWCLK") (class "Default")
      (node (ref "JP2") (pin "1") (pinfunction "1_1") (pintype "passive"))
      (node (ref "U$1") (pin "P37") (pinfunction "PA14_P37") (pintype "bidirectional"))
    )
    (net (code "50") (name "SWDIO") (class "Default")
      (node (ref "JP2") (pin "3") (pinfunction "3_3") (pintype "passive"))
      (node (ref "U$1") (pin "P34") (pinfunction "PA13_P34") (pintype "bidirectional"))
    )
    (net (code "51") (name "USB_DM") (class "Default")
      (node (ref "U$1") (pin "P32") (pinfunction "PA11_P32") (pintype "bidirectional"))
      (node (ref "U$12") (pin "P1") (pinfunction "IO1_P1") (pintype "bidirectional"))
      (node (ref "U$3") (pin "P2") (pinfunction "DM_P2") (pintype "bidirectional"))
    )
    (net (code "52") (name "USB_DP") (class "Default")
      (node (ref "U$1") (pin "P33") (pinfunction "PA12_P33") (pintype "bidirectional"))
      (node (ref "U$12") (pin "P3") (pinfunction "IO2_P3") (pintype "bidirectional"))
      (node (ref "U$3") (pin "P3") (pinfunction "DP_P3") (pintype "bidirectional"))
    )
    (net (code "53") (name "VUSB") (class "Default")
      (node (ref "C16") (pin "1") (pinfunction "1_1") (pintype "passive"))
      (node (ref "C17") (pin "P$1") (pinfunction "P$1_P$1") (pintype "passive"))
      (node (ref "C18") (pin "P$1") (pinfunction "P$1_P$1") (pintype "passive"))
      (node (ref "D2") (pin "2") (pinfunction "2_2") (pintype "bidirectional"))
      (node (ref "IC1") (pin "4") (pinfunction "V+_4") (pintype "power_in"))
      (node (ref "JP1") (pin "5") (pinfunction "5_5") (pintype "passive"))
      (node (ref "L1") (pin "1") (pinfunction "1_1") (pintype "passive"))
      (node (ref "R19") (pin "1") (pinfunction "1_1") (pintype "passive"))
      (node (ref "U$10") (pin "CATHODE") (pinfunction "CATHODE_CATHODE") (pintype "bidirectional"))
      (node (ref "U$11") (pin "P5") (pinfunction "VCC_P5") (pintype "power_in"))
      (node (ref "U$12") (pin "P5") (pinfunction "VCC_P5") (pintype "power_in"))
      (node (ref "U$13") (pin "CATHODE") (pinfunction "CATHODE_CATHODE") (pintype "bidirectional"))
      (node (ref "U$14") (pin "P$1") (pinfunction "P$1_P$1") (pintype "bidirectional"))
      (node (ref "U$2") (pin "2") (pinfunction "P2_2") (pintype "power_in"))
      (node (ref "U$4") (pin "2") (pinfunction "P2_2") (pintype "power_in"))
      (node (ref "U$5") (pin "2") (pinfunction "P2_2") (pintype "power_in"))
      (node (ref "U$6") (pin "2") (pinfunction "P2_2") (pintype "power_in"))
      (node (ref "U$8") (pin "5") (pinfunction "VIN_5") (pintype "bidirectional"))
    )
    (net (code "54") (name "XBARDUAL_OUT") (class "Default")
      (node (ref "C6") (pin "1") (pinfunction "1_1") (pintype "passive"))
      (node (ref "R10") (pin "2") (pinfunction "2_2") (pintype "passive"))
      (node (ref "R27") (pin "1") (pinfunction "1_1") (pintype "passive"))
      (node (ref "R28") (pin "2") (pinfunction "2_2") (pintype "passive"))
      (node (ref "R9") (pin "2") (pinfunction "2_2") (pintype "passive"))
      (node (ref "U$5") (pin "3") (pinfunction "P3_3") (pintype "bidirectional"))
    )
    (net (code "55") (name "XCOARSE_IN") (class "Default")
      (node (ref "IC3") (pin "5") (pinfunction "I_5") (pintype "input"))
      (node (ref "R5") (pin "1") (pinfunction "1_1") (pintype "passive"))
      (node (ref "U$1") (pin "P38") (pinfunction "PA15_P38") (pintype "bidirectional"))
    )
    (net (code "56") (name "XDUAL_OUT") (class "Default")
      (node (ref "IC1") (pin "1") (pinfunction "OUT_1") (pintype "output"))
      (node (ref "IC1") (pin "2") (pinfunction "-IN_2") (pintype "input"))
      (node (ref "U$2") (pin "3") (pinfunction "P3_3") (pintype "bidirectional"))
    )
    (net (code "57") (name "XFINE_IN") (class "Default")
      (node (ref "IC3") (pin "9") (pinfunction "I_9") (pintype "input"))
      (node (ref "R31") (pin "1") (pinfunction "1_1") (pintype "passive"))
      (node (ref "R6") (pin "1") (pinfunction "1_1") (pintype "passive"))
      (node (ref "U$1") (pin "P39") (pinfunction "PB3_P39") (pintype "bidirectional"))
    )
    (net (code "58") (name "YBARDUAL_OUT") (class "Default")
      (node (ref "C7") (pin "1") (pinfunction "1_1") (pintype "passive"))
      (node (ref "R11") (pin "2") (pinfunction "2_2") (pintype "passive"))
      (node (ref "R12") (pin "2") (pinfunction "2_2") (pintype "passive"))
      (node (ref "R29") (pin "1") (pinfunction "1_1") (pintype "passive"))
      (node (ref "R30") (pin "2") (pinfunction "2_2") (pintype "passive"))
      (node (ref "U$6") (pin "3") (pinfunction "P3_3") (pintype "bidirectional"))
    )
    (net (code "59") (name "YCOARSE_IN") (class "Default")
      (node (ref "IC3") (pin "11") (pinfunction "I_11") (pintype "input"))
      (node (ref "R7") (pin "1") (pinfunction "1_1") (pintype "passive"))
      (node (ref "U$1") (pin "P21") (pinfunction "PB10_P21") (pintype "bidirectional"))
    )
    (net (code "60") (name "YDUAL_OUT") (class "Default")
      (node (ref "C5") (pin "1") (pinfunction "1_1") (pintype "passive"))
      (node (ref "R24") (pin "1") (pinfunction "1_1") (pintype "passive"))
      (node (ref "R26") (pin "2") (pinfunction "2_2") (pintype "passive"))
      (node (ref "R7") (pin "2") (pinfunction "2_2") (pintype "passive"))
      (node (ref "R8") (pin "2") (pinfunction "2_2") (pintype "passive"))
      (node (ref "U$4") (pin "3") (pinfunction "P3_3") (pintype "bidirectional"))
    )
    (net (code "61") (name "YFINE_IN") (class "Default")
      (node (ref "IC3") (pin "13") (pinfunction "I_13") (pintype "input"))
      (node (ref "R8") (pin "1") (pinfunction "1_1") (pintype "passive"))
      (node (ref "U$1") (pin "P22") (pinfunction "PB11_P22") (pintype "bidirectional"))
    )
    (net (code "62") (name "unconnected-(IC1B-+IN-Pad5)") (class "Default")
      (node (ref "IC1") (pin "5") (pinfunction "+IN_5") (pintype "input"))
    )
    (net (code "63") (name "unconnected-(IC1B--IN-Pad6)") (class "Default")
      (node (ref "IC1") (pin "6") (pinfunction "-IN_6") (pintype "input"))
    )
    (net (code "64") (name "unconnected-(IC1B-OUT-Pad7)") (class "Default")
      (node (ref "IC1") (pin "7") (pinfunction "OUT_7") (pintype "output"))
    )
    (net (code "65") (name "unconnected-(IC1C-+IN-Pad10)") (class "Default")
      (node (ref "IC1") (pin "10") (pinfunction "+IN_10") (pintype "input"))
    )
    (net (code "66") (name "unconnected-(IC1C--IN-Pad9)") (class "Default")
      (node (ref "IC1") (pin "9") (pinfunction "-IN_9") (pintype "input"))
    )
    (net (code "67") (name "unconnected-(IC1C-OUT-Pad8)") (class "Default")
      (node (ref "IC1") (pin "8") (pinfunction "OUT_8") (pintype "output"))
    )
    (net (code "68") (name "unconnected-(IC1D-+IN-Pad12)") (class "Default")
      (node (ref "IC1") (pin "12") (pinfunction "+IN_12") (pintype "input"))
    )
    (net (code "69") (name "unconnected-(IC1D--IN-Pad13)") (class "Default")
      (node (ref "IC1") (pin "13") (pinfunction "-IN_13") (pintype "input"))
    )
    (net (code "70") (name "unconnected-(IC1D-OUT-Pad14)") (class "Default")
      (node (ref "IC1") (pin "14") (pinfunction "OUT_14") (pintype "output"))
    )
    (net (code "71") (name "unconnected-(IC3A-O-Pad2)") (class "Default")
      (node (ref "IC3") (pin "2") (pinfunction "O_2") (pintype "output"))
    )
    (net (code "72") (name "unconnected-(IC3B-O-Pad4)") (class "Default")
      (node (ref "IC3") (pin "4") (pinfunction "O_4") (pintype "output"))
    )
    (net (code "73") (name "unconnected-(U$1-PA4-PadP14)") (class "Default")
      (node (ref "U$1") (pin "P14") (pinfunction "PA4_P14") (pintype "bidirectional"))
    )
    (net (code "74") (name "unconnected-(U$1-PA8-PadP29)") (class "Default")
      (node (ref "U$1") (pin "P29") (pinfunction "PA8_P29") (pintype "bidirectional"))
    )
    (net (code "75") (name "unconnected-(U$1-PA9-PadP30)") (class "Default")
      (node (ref "U$1") (pin "P30") (pinfunction "PA9_P30") (pintype "bidirectional"))
    )
    (net (code "76") (name "unconnected-(U$1-PA10-PadP31)") (class "Default")
      (node (ref "U$1") (pin "P31") (pinfunction "PA10_P31") (pintype "bidirectional"))
    )
    (net (code "77") (name "unconnected-(U$1-PB1-PadP19)") (class "Default")
      (node (ref "U$1") (pin "P19") (pinfunction "PB1_P19") (pintype "bidirectional"))
    )
    (net (code "78") (name "unconnected-(U$1-PB2-PadP20)") (class "Default")
      (node (ref "U$1") (pin "P20") (pinfunction "PB2_P20") (pintype "bidirectional"))
    )
    (net (code "79") (name "unconnected-(U$1-PB5-PadP41)") (class "Default")
      (node (ref "U$1") (pin "P41") (pinfunction "PB5_P41") (pintype "bidirectional"))
    )
    (net (code "80") (name "unconnected-(U$1-PB6-PadP42)") (class "Default")
      (node (ref "U$1") (pin "P42") (pinfunction "PB6_P42") (pintype "bidirectional"))
    )
    (net (code "81") (name "unconnected-(U$1-PB7-PadP43)") (class "Default")
      (node (ref "U$1") (pin "P43") (pinfunction "PB7_P43") (pintype "bidirectional"))
    )
    (net (code "82") (name "unconnected-(U$1-PB8-PadP45)") (class "Default")
      (node (ref "U$1") (pin "P45") (pinfunction "PB8_P45") (pintype "bidirectional"))
    )
    (net (code "83") (name "unconnected-(U$1-PB9-PadP46)") (class "Default")
      (node (ref "U$1") (pin "P46") (pinfunction "PB9_P46") (pintype "bidirectional"))
    )
    (net (code "84") (name "unconnected-(U$1-PC13-PadP2)") (class "Default")
      (node (ref "U$1") (pin "P2") (pinfunction "PC13_P2") (pintype "bidirectional"))
    )
    (net (code "85") (name "unconnected-(U$1-PC14-PadP3)") (class "Default")
      (node (ref "U$1") (pin "P3") (pinfunction "PC14_P3") (pintype "bidirectional"))
    )
    (net (code "86") (name "unconnected-(U$1-PC15-PadP4)") (class "Default")
      (node (ref "U$1") (pin "P4") (pinfunction "PC15_P4") (pintype "bidirectional"))
    )
    (net (code "87") (name "unconnected-(U$12-IO3-PadP4)") (class "Default")
      (node (ref "U$12") (pin "P4") (pinfunction "IO3_P4") (pintype "bidirectional"))
    )
    (net (code "88") (name "unconnected-(U$12-IO4-PadP6)") (class "Default")
      (node (ref "U$12") (pin "P6") (pinfunction "IO4_P6") (pintype "bidirectional"))
    )
  )
)
